# Wattuino-Uno_v11.net
KiCad netlist of a schematic drawn in EAGLE
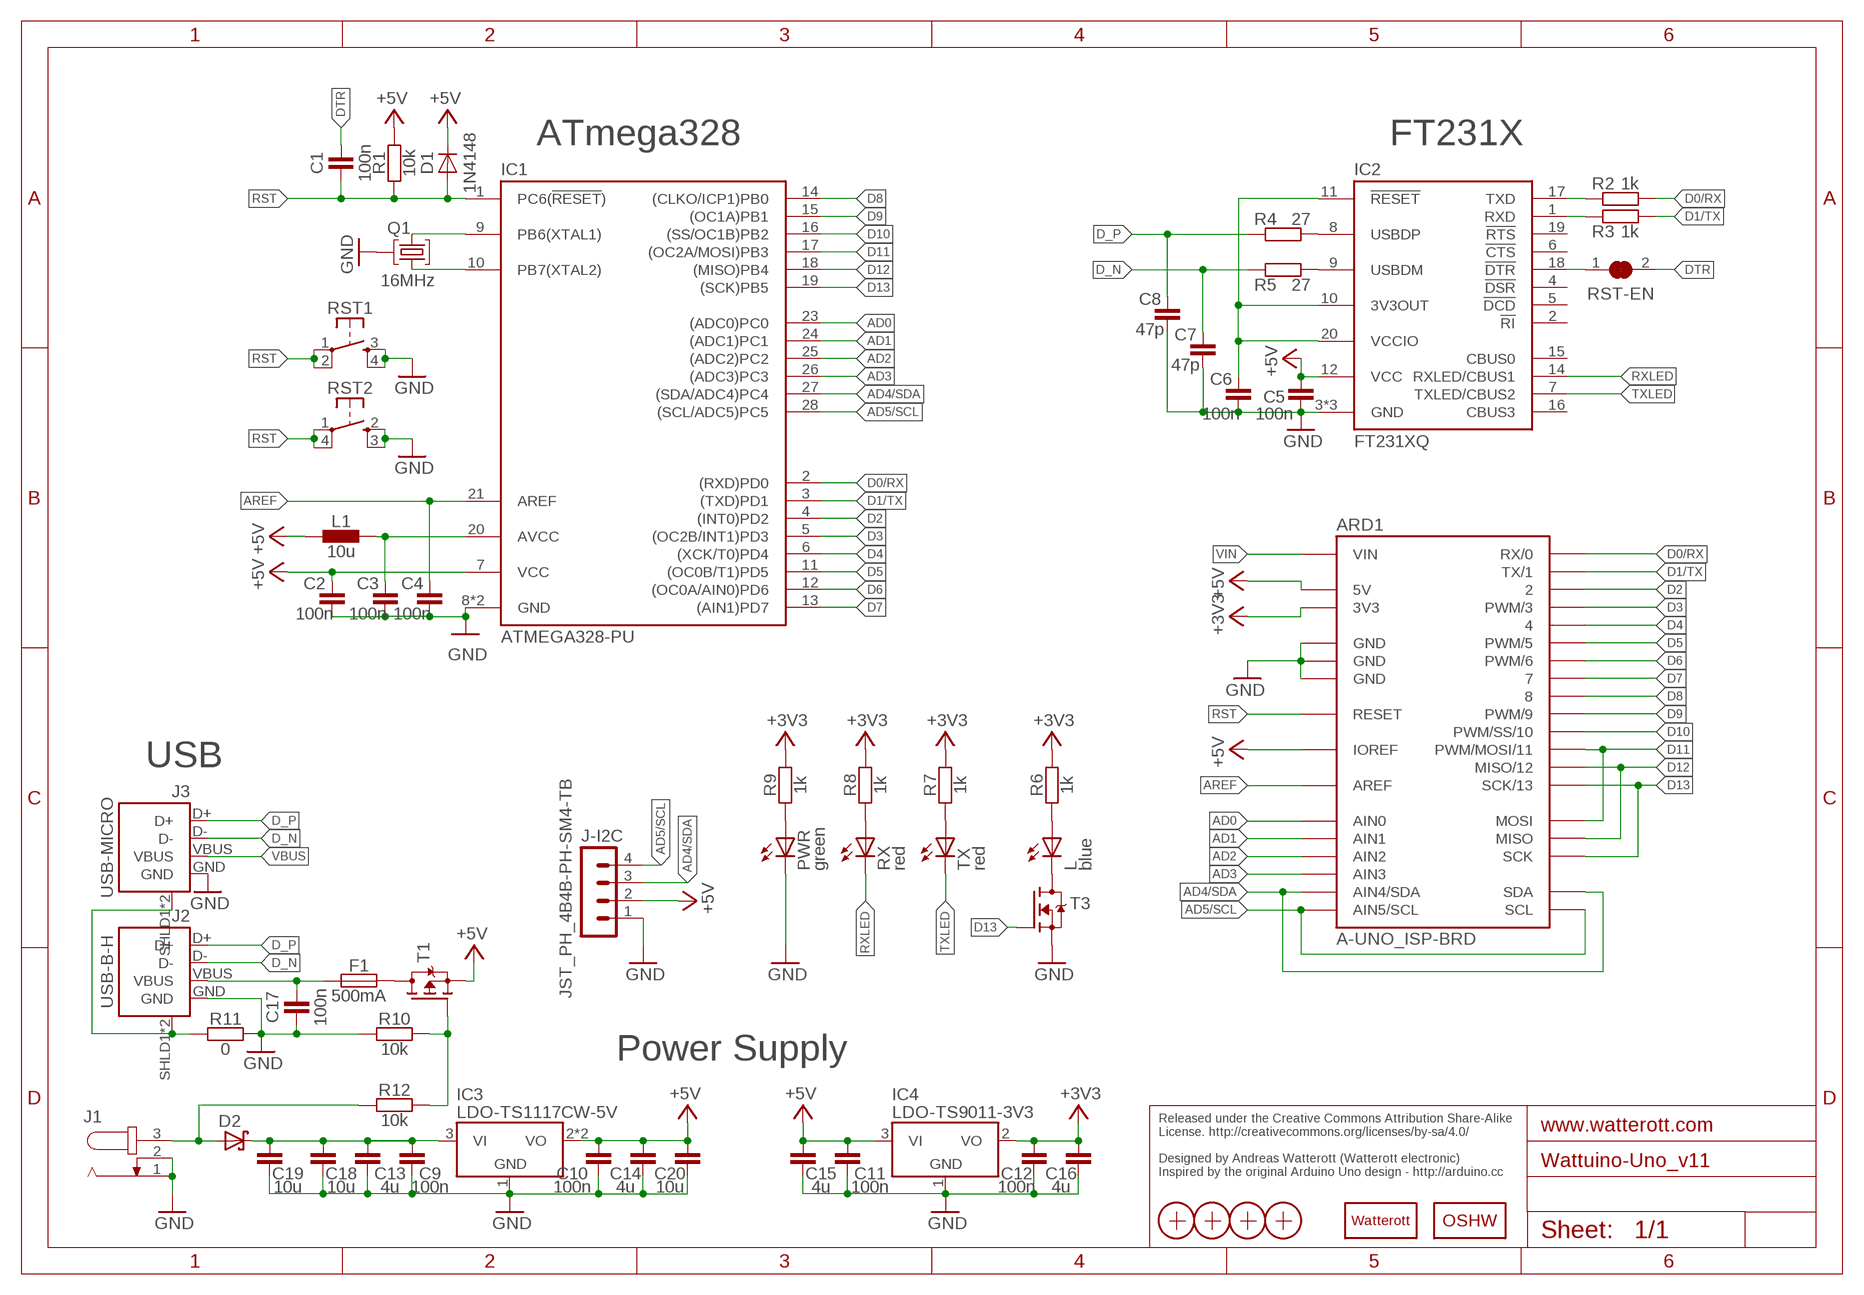
[diagram p0: schematic, sheet 1]

(export (version "E")
  (design (tool "Eeschema 10.0.6"))
  (components
    (comp (ref "ARD1")
      (value "A-UNO_ISP-BRD")
      (footprint "eagle-import:A-UNO-ISP")
      (libsource (lib "eagle-import") (part "A-UNO_ISP-BRD"))
    )
    (comp (ref "C1")
      (value "100n")
      (footprint "eagle-import:C0402")
      (libsource (lib "eagle-import") (part "CAPACITOR-0402"))
    )
    (comp (ref "C2")
      (value "100n")
      (footprint "eagle-import:C0402")
      (libsource (lib "eagle-import") (part "CAPACITOR-0402"))
    )
    (comp (ref "C3")
      (value "100n")
      (footprint "eagle-import:C0402")
      (libsource (lib "eagle-import") (part "CAPACITOR-0402"))
    )
    (comp (ref "C4")
      (value "100n")
      (footprint "eagle-import:C0402")
      (libsource (lib "eagle-import") (part "CAPACITOR-0402"))
    )
    (comp (ref "C5")
      (value "100n")
      (footprint "eagle-import:C0402")
      (libsource (lib "eagle-import") (part "CAPACITOR-0402"))
    )
    (comp (ref "C6")
      (value "100n")
      (footprint "eagle-import:C0402")
      (libsource (lib "eagle-import") (part "CAPACITOR-0402"))
    )
    (comp (ref "C7")
      (value "47p")
      (footprint "eagle-import:C0402")
      (libsource (lib "eagle-import") (part "CAPACITOR-0402"))
    )
    (comp (ref "C8")
      (value "47p")
      (footprint "eagle-import:C0402")
      (libsource (lib "eagle-import") (part "CAPACITOR-0402"))
    )
    (comp (ref "C9")
      (value "100n")
      (footprint "eagle-import:C0402")
      (libsource (lib "eagle-import") (part "CAPACITOR-0402"))
    )
    (comp (ref "C10")
      (value "100n")
      (footprint "eagle-import:C0402")
      (libsource (lib "eagle-import") (part "CAPACITOR-0402"))
    )
    (comp (ref "C11")
      (value "100n")
      (footprint "eagle-import:C0402")
      (libsource (lib "eagle-import") (part "CAPACITOR-0402"))
    )
    (comp (ref "C12")
      (value "100n")
      (footprint "eagle-import:C0402")
      (libsource (lib "eagle-import") (part "CAPACITOR-0402"))
    )
    (comp (ref "C13")
      (value "4u")
      (footprint "eagle-import:C0603")
      (libsource (lib "eagle-import") (part "CAPACITOR-0603"))
    )
    (comp (ref "C14")
      (value "4u")
      (footprint "eagle-import:C0603")
      (libsource (lib "eagle-import") (part "CAPACITOR-0603"))
    )
    (comp (ref "C15")
      (value "4u")
      (footprint "eagle-import:C0603")
      (libsource (lib "eagle-import") (part "CAPACITOR-0603"))
    )
    (comp (ref "C16")
      (value "4u")
      (footprint "eagle-import:C0603")
      (libsource (lib "eagle-import") (part "CAPACITOR-0603"))
    )
    (comp (ref "C17")
      (value "100n")
      (footprint "eagle-import:C0402")
      (libsource (lib "eagle-import") (part "CAPACITOR-0402"))
    )
    (comp (ref "C18")
      (value "10u")
      (footprint "eagle-import:C1206")
      (libsource (lib "eagle-import") (part "CAPACITOR-1206"))
    )
    (comp (ref "C19")
      (value "10u")
      (footprint "eagle-import:C1206")
      (libsource (lib "eagle-import") (part "CAPACITOR-1206"))
    )
    (comp (ref "C20")
      (value "10u")
      (footprint "eagle-import:C1206")
      (libsource (lib "eagle-import") (part "CAPACITOR-1206"))
    )
    (comp (ref "D1")
      (value "1N4148")
      (footprint "eagle-import:SOD110")
      (libsource (lib "eagle-import") (part "DIODE-SOD110"))
    )
    (comp (ref "D2")
      (value "D_SCHOTTKY-SMA")
      (footprint "eagle-import:SMA_DO214AC")
      (libsource (lib "eagle-import") (part "D_SCHOTTKY-SMA"))
    )
    (comp (ref "F1")
      (value "500mA")
      (footprint "eagle-import:C0805")
      (libsource (lib "eagle-import") (part "FUSE-0805"))
    )
    (comp (ref "IC1")
      (value "ATMEGA328-PU")
      (footprint "eagle-import:DIL28")
      (libsource (lib "eagle-import") (part "ATMEGA328-PU"))
    )
    (comp (ref "IC2")
      (value "FT231XQ")
      (footprint "eagle-import:QFN20-PAD")
      (libsource (lib "eagle-import") (part "FT231XQ"))
    )
    (comp (ref "IC3")
      (value "LDO-TS1117CW-5V")
      (footprint "eagle-import:SOT223")
      (libsource (lib "eagle-import") (part "LDO-TS1117CW-5V"))
    )
    (comp (ref "IC4")
      (value "LDO-TS9011-3V3")
      (footprint "eagle-import:SOT23")
      (libsource (lib "eagle-import") (part "LDO-TS9011-3V3"))
    )
    (comp (ref "J-I2C")
      (value "JST_PH_4B4B-PH-SM4-TB")
      (footprint "eagle-import:JST_B4B-PH-SM4-TB")
      (libsource (lib "eagle-import") (part "JST_PH_4B4B-PH-SM4-TB"))
    )
    (comp (ref "J1")
      (value "DC-JACK")
      (footprint "eagle-import:DC-JACK")
      (libsource (lib "eagle-import") (part "DC-JACK"))
    )
    (comp (ref "J2")
      (value "USB-B-H")
      (footprint "eagle-import:USB-B-H")
      (libsource (lib "eagle-import") (part "USB-B-H"))
    )
    (comp (ref "J3")
      (value "USB-MICRO")
      (footprint "eagle-import:USB-MICRO-10103594")
      (libsource (lib "eagle-import") (part "USB-MICRO"))
    )
    (comp (ref "L")
      (value "blue")
      (footprint "eagle-import:C0603")
      (libsource (lib "eagle-import") (part "LED-0603"))
    )
    (comp (ref "L1")
      (value "10u")
      (footprint "eagle-import:C0603")
      (libsource (lib "eagle-import") (part "INDUCTOR-0603"))
    )
    (comp (ref "LOGO1")
      (value "LOGO-S_PLACE_M")
      (footprint "eagle-import:SPARK_TPLACE_M")
      (libsource (lib "eagle-import") (part "LOGO-S_PLACE_M"))
    )
    (comp (ref "LOGO2")
      (value "OSHW_LOGOX0100")
      (footprint "eagle-import:OSHW_6X100")
      (libsource (lib "eagle-import") (part "OSHW_LOGOX0100"))
    )
    (comp (ref "PWR")
      (value "green")
      (footprint "eagle-import:C0603")
      (libsource (lib "eagle-import") (part "LED-0603"))
    )
    (comp (ref "Q1")
      (value "16MHz")
      (footprint "eagle-import:CRYSTAL_32X13")
      (libsource (lib "eagle-import") (part "CRYSTAL-RES-32"))
    )
    (comp (ref "R1")
      (value "10k")
      (footprint "eagle-import:C0402")
      (libsource (lib "eagle-import") (part "RESISTOR-0402"))
    )
    (comp (ref "R2")
      (value "1k")
      (footprint "eagle-import:C0402")
      (libsource (lib "eagle-import") (part "RESISTOR-0402"))
    )
    (comp (ref "R3")
      (value "1k")
      (footprint "eagle-import:C0402")
      (libsource (lib "eagle-import") (part "RESISTOR-0402"))
    )
    (comp (ref "R4")
      (value "27")
      (footprint "eagle-import:C0402")
      (libsource (lib "eagle-import") (part "RESISTOR-0402"))
    )
    (comp (ref "R5")
      (value "27")
      (footprint "eagle-import:C0402")
      (libsource (lib "eagle-import") (part "RESISTOR-0402"))
    )
    (comp (ref "R6")
      (value "1k")
      (footprint "eagle-import:C0402")
      (libsource (lib "eagle-import") (part "RESISTOR-0402"))
    )
    (comp (ref "R7")
      (value "1k")
      (footprint "eagle-import:C0402")
      (libsource (lib "eagle-import") (part "RESISTOR-0402"))
    )
    (comp (ref "R8")
      (value "1k")
      (footprint "eagle-import:C0402")
      (libsource (lib "eagle-import") (part "RESISTOR-0402"))
    )
    (comp (ref "R9")
      (value "1k")
      (footprint "eagle-import:C0402")
      (libsource (lib "eagle-import") (part "RESISTOR-0402"))
    )
    (comp (ref "R10")
      (value "10k")
      (footprint "eagle-import:C0402")
      (libsource (lib "eagle-import") (part "RESISTOR-0402"))
    )
    (comp (ref "R11")
      (value "0")
      (footprint "eagle-import:C0402")
      (libsource (lib "eagle-import") (part "RESISTOR-0402"))
    )
    (comp (ref "R12")
      (value "10k")
      (footprint "eagle-import:C0402")
      (libsource (lib "eagle-import") (part "RESISTOR-0402"))
    )
    (comp (ref "RST-EN")
      (value "JUMPER2-0603")
      (footprint "eagle-import:JUMPER2-0603")
      (libsource (lib "eagle-import") (part "JUMPER2-0603"))
    )
    (comp (ref "RST1")
      (value "SW-TACTILE-PTS840P")
      (footprint "eagle-import:PTS840P")
      (libsource (lib "eagle-import") (part "SW-TACTILE-PTS840P"))
    )
    (comp (ref "RST2")
      (value "SW-TACTILE-TL3315")
      (footprint "eagle-import:TL3315N")
      (libsource (lib "eagle-import") (part "SW-TACTILE-TL3315"))
    )
    (comp (ref "RX")
      (value "red")
      (footprint "eagle-import:C0603")
      (libsource (lib "eagle-import") (part "LED-0603"))
    )
    (comp (ref "T1")
      (value "MOSFET-P-SOT23")
      (footprint "eagle-import:SOT23")
      (libsource (lib "eagle-import") (part "MOSFET-P-SOT23"))
    )
    (comp (ref "T3")
      (value "MOSFET-N-SOT23")
      (footprint "eagle-import:SOT23")
      (libsource (lib "eagle-import") (part "MOSFET-N-SOT23"))
    )
    (comp (ref "TX")
      (value "red")
      (footprint "eagle-import:C0603")
      (libsource (lib "eagle-import") (part "LED-0603"))
    )
    (comp (ref "X1")
      (value "PASSER-07")
      (footprint "eagle-import:PASSER_07MM")
      (libsource (lib "eagle-import") (part "PASSER-07"))
    )
    (comp (ref "X2")
      (value "PASSER-07")
      (footprint "eagle-import:PASSER_07MM")
      (libsource (lib "eagle-import") (part "PASSER-07"))
    )
    (comp (ref "X3")
      (value "PASSER-07")
      (footprint "eagle-import:PASSER_07MM")
      (libsource (lib "eagle-import") (part "PASSER-07"))
    )
    (comp (ref "X4")
      (value "PASSER-07")
      (footprint "eagle-import:PASSER_07MM")
      (libsource (lib "eagle-import") (part "PASSER-07"))
    )
  )
  (nets
    (net (code "1") (name "+3V3") (class "Default")
      (node (ref "ARD1") (pin "3V3") (pinfunction "3V3_3V3") (pintype "power_in"))
      (node (ref "C12") (pin "2") (pinfunction "2_2") (pintype "passive"))
      (node (ref "C16") (pin "2") (pinfunction "2_2") (pintype "passive"))
      (node (ref "IC4") (pin "2") (pinfunction "VO_2") (pintype "passive"))
      (node (ref "R6") (pin "2") (pinfunction "2_2") (pintype "passive"))
      (node (ref "R7") (pin "2") (pinfunction "2_2") (pintype "passive"))
      (node (ref "R8") (pin "2") (pinfunction "2_2") (pintype "passive"))
      (node (ref "R9") (pin "2") (pinfunction "2_2") (pintype "passive"))
    )
    (net (code "2") (name "+5V") (class "Default")
      (node (ref "ARD1") (pin "5V") (pinfunction "5V_5V") (pintype "power_in"))
      (node (ref "ARD1") (pin "IOREF") (pinfunction "IOREF_IOREF") (pintype "power_in"))
      (node (ref "ARD1") (pin "VCC") (pinfunction "5V_VCC") (pintype "power_in"))
      (node (ref "C10") (pin "2") (pinfunction "2_2") (pintype "passive"))
      (node (ref "C11") (pin "2") (pinfunction "2_2") (pintype "passive"))
      (node (ref "C14") (pin "2") (pinfunction "2_2") (pintype "passive"))
      (node (ref "C15") (pin "2") (pinfunction "2_2") (pintype "passive"))
      (node (ref "C2") (pin "2") (pinfunction "2_2") (pintype "passive"))
      (node (ref "C20") (pin "2") (pinfunction "2_2") (pintype "passive"))
      (node (ref "C5") (pin "2") (pinfunction "2_2") (pintype "passive"))
      (node (ref "D1") (pin "C") (pinfunction "C_C") (pintype "passive"))
      (node (ref "IC1") (pin "7") (pinfunction "VCC_7") (pintype "power_in"))
      (node (ref "IC2") (pin "12") (pinfunction "VCC_12") (pintype "power_in"))
      (node (ref "IC3") (pin "2") (pinfunction "VO_2") (pintype "passive"))
      (node (ref "IC3") (pin "4") (pinfunction "VO_4") (pintype "passive"))
      (node (ref "IC4") (pin "3") (pinfunction "VI_3") (pintype "input"))
      (node (ref "J-I2C") (pin "2") (pinfunction "2_2") (pintype "passive"))
      (node (ref "L1") (pin "1") (pinfunction "1_1") (pintype "passive"))
      (node (ref "R1") (pin "2") (pinfunction "2_2") (pintype "passive"))
      (node (ref "T1") (pin "2") (pinfunction "S_2") (pintype "passive"))
    )
    (net (code "3") (name "AD0") (class "Default")
      (node (ref "ARD1") (pin "A0") (pinfunction "AIN0_A0") (pintype "bidirectional"))
      (node (ref "IC1") (pin "23") (pinfunction "(ADC0)PC0_23") (pintype "bidirectional"))
    )
    (net (code "4") (name "AD1") (class "Default")
      (node (ref "ARD1") (pin "A1") (pinfunction "AIN1_A1") (pintype "bidirectional"))
      (node (ref "IC1") (pin "24") (pinfunction "(ADC1)PC1_24") (pintype "bidirectional"))
    )
    (net (code "5") (name "AD2") (class "Default")
      (node (ref "ARD1") (pin "A2") (pinfunction "AIN2_A2") (pintype "bidirectional"))
      (node (ref "IC1") (pin "25") (pinfunction "(ADC2)PC2_25") (pintype "bidirectional"))
    )
    (net (code "6") (name "AD3") (class "Default")
      (node (ref "ARD1") (pin "A3") (pinfunction "AIN3_A3") (pintype "bidirectional"))
      (node (ref "IC1") (pin "26") (pinfunction "(ADC3)PC3_26") (pintype "bidirectional"))
    )
    (net (code "7") (name "AD4{slash}SDA") (class "Default")
      (node (ref "ARD1") (pin "A4") (pinfunction "AIN4/SDA_A4") (pintype "bidirectional"))
      (node (ref "ARD1") (pin "SDA") (pinfunction "SDA_SDA") (pintype "bidirectional"))
      (node (ref "IC1") (pin "27") (pinfunction "(SDA/ADC4)PC4_27") (pintype "bidirectional"))
      (node (ref "J-I2C") (pin "3") (pinfunction "3_3") (pintype "passive"))
    )
    (net (code "8") (name "AD5{slash}SCL") (class "Default")
      (node (ref "ARD1") (pin "A5") (pinfunction "AIN5/SCL_A5") (pintype "bidirectional"))
      (node (ref "ARD1") (pin "SCL") (pinfunction "SCL_SCL") (pintype "bidirectional"))
      (node (ref "IC1") (pin "28") (pinfunction "(SCL/ADC5)PC5_28") (pintype "bidirectional"))
      (node (ref "J-I2C") (pin "4") (pinfunction "4_4") (pintype "passive"))
    )
    (net (code "9") (name "AREF") (class "Default")
      (node (ref "ARD1") (pin "AREF") (pinfunction "AREF_AREF") (pintype "power_in"))
      (node (ref "C4") (pin "2") (pinfunction "2_2") (pintype "passive"))
      (node (ref "IC1") (pin "21") (pinfunction "AREF_21") (pintype "passive"))
    )
    (net (code "10") (name "D0{slash}RX") (class "Default")
      (node (ref "ARD1") (pin "0") (pinfunction "RX/0_0") (pintype "bidirectional"))
      (node (ref "IC1") (pin "2") (pinfunction "(RXD)PD0_2") (pintype "bidirectional"))
      (node (ref "R2") (pin "2") (pinfunction "2_2") (pintype "passive"))
    )
    (net (code "11") (name "D1{slash}TX") (class "Default")
      (node (ref "ARD1") (pin "1") (pinfunction "TX/1_1") (pintype "bidirectional"))
      (node (ref "IC1") (pin "3") (pinfunction "(TXD)PD1_3") (pintype "bidirectional"))
      (node (ref "R3") (pin "2") (pinfunction "2_2") (pintype "passive"))
    )
    (net (code "12") (name "D2") (class "Default")
      (node (ref "ARD1") (pin "2") (pinfunction "2_2") (pintype "bidirectional"))
      (node (ref "IC1") (pin "4") (pinfunction "(INT0)PD2_4") (pintype "bidirectional"))
    )
    (net (code "13") (name "D3") (class "Default")
      (node (ref "ARD1") (pin "3") (pinfunction "PWM/3_3") (pintype "bidirectional"))
      (node (ref "IC1") (pin "5") (pinfunction "(OC2B/INT1)PD3_5") (pintype "bidirectional"))
    )
    (net (code "14") (name "D4") (class "Default")
      (node (ref "ARD1") (pin "4") (pinfunction "4_4") (pintype "bidirectional"))
      (node (ref "IC1") (pin "6") (pinfunction "(XCK/T0)PD4_6") (pintype "bidirectional"))
    )
    (net (code "15") (name "D5") (class "Default")
      (node (ref "ARD1") (pin "5") (pinfunction "PWM/5_5") (pintype "bidirectional"))
      (node (ref "IC1") (pin "11") (pinfunction "(OC0B/T1)PD5_11") (pintype "bidirectional"))
    )
    (net (code "16") (name "D6") (class "Default")
      (node (ref "ARD1") (pin "6") (pinfunction "PWM/6_6") (pintype "bidirectional"))
      (node (ref "IC1") (pin "12") (pinfunction "(OC0A/AIN0)PD6_12") (pintype "bidirectional"))
    )
    (net (code "17") (name "D7") (class "Default")
      (node (ref "ARD1") (pin "7") (pinfunction "7_7") (pintype "bidirectional"))
      (node (ref "IC1") (pin "13") (pinfunction "(AIN1)PD7_13") (pintype "bidirectional"))
    )
    (net (code "18") (name "D8") (class "Default")
      (node (ref "ARD1") (pin "8") (pinfunction "8_8") (pintype "bidirectional"))
      (node (ref "IC1") (pin "14") (pinfunction "(CLKO/ICP1)PB0_14") (pintype "bidirectional"))
    )
    (net (code "19") (name "D9") (class "Default")
      (node (ref "ARD1") (pin "9") (pinfunction "PWM/9_9") (pintype "bidirectional"))
      (node (ref "IC1") (pin "15") (pinfunction "(OC1A)PB1_15") (pintype "bidirectional"))
    )
    (net (code "20") (name "D10") (class "Default")
      (node (ref "ARD1") (pin "10") (pinfunction "PWM/SS/10_10") (pintype "bidirectional"))
      (node (ref "IC1") (pin "16") (pinfunction "(SS/OC1B)PB2_16") (pintype "bidirectional"))
    )
    (net (code "21") (name "D11") (class "Default")
      (node (ref "ARD1") (pin "11") (pinfunction "PWM/MOSI/11_11") (pintype "bidirectional"))
      (node (ref "ARD1") (pin "MOSI") (pinfunction "MOSI_MOSI") (pintype "bidirectional"))
      (node (ref "IC1") (pin "17") (pinfunction "(OC2A/MOSI)PB3_17") (pintype "bidirectional"))
    )
    (net (code "22") (name "D12") (class "Default")
      (node (ref "ARD1") (pin "12") (pinfunction "MISO/12_12") (pintype "bidirectional"))
      (node (ref "ARD1") (pin "MISO") (pinfunction "MISO_MISO") (pintype "bidirectional"))
      (node (ref "IC1") (pin "18") (pinfunction "(MISO)PB4_18") (pintype "bidirectional"))
    )
    (net (code "23") (name "D13") (class "Default")
      (node (ref "ARD1") (pin "13") (pinfunction "SCK/13_13") (pintype "bidirectional"))
      (node (ref "ARD1") (pin "SCK") (pinfunction "SCK_SCK") (pintype "bidirectional"))
      (node (ref "IC1") (pin "19") (pinfunction "(SCK)PB5_19") (pintype "bidirectional"))
      (node (ref "T3") (pin "1") (pinfunction "G_1") (pintype "passive"))
    )
    (net (code "24") (name "DTR") (class "Default")
      (node (ref "C1") (pin "2") (pinfunction "2_2") (pintype "passive"))
      (node (ref "RST-EN") (pin "2") (pinfunction "2_2") (pintype "passive"))
    )
    (net (code "25") (name "D_N") (class "Default")
      (node (ref "C7") (pin "2") (pinfunction "2_2") (pintype "passive"))
      (node (ref "J2") (pin "D-") (pinfunction "D-_D-") (pintype "bidirectional"))
      (node (ref "J3") (pin "D-") (pinfunction "D-_D-") (pintype "bidirectional"))
      (node (ref "R5") (pin "1") (pinfunction "1_1") (pintype "passive"))
    )
    (net (code "26") (name "D_P") (class "Default")
      (node (ref "C8") (pin "2") (pinfunction "2_2") (pintype "passive"))
      (node (ref "J2") (pin "D+") (pinfunction "D+_D+") (pintype "bidirectional"))
      (node (ref "J3") (pin "D+") (pinfunction "D+_D+") (pintype "bidirectional"))
      (node (ref "R4") (pin "1") (pinfunction "1_1") (pintype "passive"))
    )
    (net (code "27") (name "GND") (class "Default")
      (node (ref "ARD1") (pin "GND@1") (pinfunction "GND_GND@1") (pintype "power_in"))
      (node (ref "ARD1") (pin "GND@2") (pinfunction "GND_GND@2") (pintype "power_in"))
      (node (ref "ARD1") (pin "GND@3") (pinfunction "GND_GND@3") (pintype "power_in"))
      (node (ref "ARD1") (pin "GND@4") (pinfunction "GND_GND@4") (pintype "power_in"))
      (node (ref "C10") (pin "1") (pinfunction "1_1") (pintype "passive"))
      (node (ref "C11") (pin "1") (pinfunction "1_1") (pintype "passive"))
      (node (ref "C12") (pin "1") (pinfunction "1_1") (pintype "passive"))
      (node (ref "C13") (pin "1") (pinfunction "1_1") (pintype "passive"))
      (node (ref "C14") (pin "1") (pinfunction "1_1") (pintype "passive"))
      (node (ref "C15") (pin "1") (pinfunction "1_1") (pintype "passive"))
      (node (ref "C16") (pin "1") (pinfunction "1_1") (pintype "passive"))
      (node (ref "C17") (pin "1") (pinfunction "1_1") (pintype "passive"))
      (node (ref "C18") (pin "1") (pinfunction "1_1") (pintype "passive"))
      (node (ref "C19") (pin "1") (pinfunction "1_1") (pintype "passive"))
      (node (ref "C2") (pin "1") (pinfunction "1_1") (pintype "passive"))
      (node (ref "C20") (pin "1") (pinfunction "1_1") (pintype "passive"))
      (node (ref "C3") (pin "1") (pinfunction "1_1") (pintype "passive"))
      (node (ref "C4") (pin "1") (pinfunction "1_1") (pintype "passive"))
      (node (ref "C5") (pin "1") (pinfunction "1_1") (pintype "passive"))
      (node (ref "C6") (pin "1") (pinfunction "1_1") (pintype "passive"))
      (node (ref "C7") (pin "1") (pinfunction "1_1") (pintype "passive"))
      (node (ref "C8") (pin "1") (pinfunction "1_1") (pintype "passive"))
      (node (ref "C9") (pin "1") (pinfunction "1_1") (pintype "passive"))
      (node (ref "IC1") (pin "22") (pinfunction "GND_22") (pintype "power_in"))
      (node (ref "IC1") (pin "8") (pinfunction "GND_8") (pintype "power_in"))
      (node (ref "IC2") (pin "13") (pinfunction "GND_13") (pintype "power_in"))
      (node (ref "IC2") (pin "3") (pinfunction "GND_3") (pintype "power_in"))
      (node (ref "IC2") (pin "TP") (pinfunction "GND_TP") (pintype "power_in"))
      (node (ref "IC3") (pin "1") (pinfunction "GND_1") (pintype "passive"))
      (node (ref "IC4") (pin "1") (pinfunction "GND_1") (pintype "passive"))
      (node (ref "J-I2C") (pin "1") (pinfunction "1_1") (pintype "passive"))
      (node (ref "J1") (pin "1") (pinfunction "1_1") (pintype "passive"))
      (node (ref "J1") (pin "2") (pinfunction "2_2") (pintype "passive"))
      (node (ref "J2") (pin "GND") (pinfunction "GND_GND") (pintype "power_in"))
      (node (ref "J3") (pin "GND") (pinfunction "GND_GND") (pintype "power_in"))
      (node (ref "PWR") (pin "C") (pinfunction "C_C") (pintype "passive"))
      (node (ref "Q1") (pin "GND") (pinfunction "GND_GND") (pintype "passive"))
      (node (ref "R10") (pin "1") (pinfunction "1_1") (pintype "passive"))
      (node (ref "R11") (pin "2") (pinfunction "2_2") (pintype "passive"))
      (node (ref "RST1") (pin "3") (pinfunction "S1_3") (pintype "passive"))
      (node (ref "RST1") (pin "4") (pinfunction "S2_4") (pintype "passive"))
      (node (ref "RST2") (pin "2") (pinfunction "S1_2") (pintype "passive"))
      (node (ref "RST2") (pin "3") (pinfunction "S2_3") (pintype "passive"))
      (node (ref "T3") (pin "2") (pinfunction "S_2") (pintype "passive"))
    )
    (net (code "28") (name "Net-(D2-PadA)") (class "Default")
      (node (ref "D2") (pin "A") (pinfunction "A_A") (pintype "passive"))
      (node (ref "J1") (pin "3") (pinfunction "3_3") (pintype "passive"))
      (node (ref "R12") (pin "1") (pinfunction "1_1") (pintype "passive"))
    )
    (net (code "29") (name "Net-(IC1-AVCC)") (class "Default")
      (node (ref "C3") (pin "2") (pinfunction "2_2") (pintype "passive"))
      (node (ref "IC1") (pin "20") (pinfunction "AVCC_20") (pintype "power_in"))
      (node (ref "L1") (pin "2") (pinfunction "2_2") (pintype "passive"))
    )
    (net (code "30") (name "Net-(IC1-PB6(XTAL1))") (class "Default")
      (node (ref "IC1") (pin "9") (pinfunction "PB6(XTAL1)_9") (pintype "bidirectional"))
      (node (ref "Q1") (pin "2") (pinfunction "2_2") (pintype "passive"))
    )
    (net (code "31") (name "Net-(IC1-PB7(XTAL2))") (class "Default")
      (node (ref "IC1") (pin "10") (pinfunction "PB7(XTAL2)_10") (pintype "bidirectional"))
      (node (ref "Q1") (pin "1") (pinfunction "1_1") (pintype "passive"))
    )
    (net (code "32") (name "Net-(IC2-3V3OUT)") (class "Default")
      (node (ref "C6") (pin "2") (pinfunction "2_2") (pintype "passive"))
      (node (ref "IC2") (pin "10") (pinfunction "3V3OUT_10") (pintype "power_in"))
      (node (ref "IC2") (pin "11") (pinfunction "~{RESET}_11") (pintype "bidirectional"))
      (node (ref "IC2") (pin "20") (pinfunction "VCCIO_20") (pintype "power_in"))
    )
    (net (code "33") (name "Net-(IC2-RXD)") (class "Default")
      (node (ref "IC2") (pin "1") (pinfunction "RXD_1") (pintype "bidirectional"))
      (node (ref "R3") (pin "1") (pinfunction "1_1") (pintype "passive"))
    )
    (net (code "34") (name "Net-(IC2-TXD)") (class "Default")
      (node (ref "IC2") (pin "17") (pinfunction "TXD_17") (pintype "bidirectional"))
      (node (ref "R2") (pin "1") (pinfunction "1_1") (pintype "passive"))
    )
    (net (code "35") (name "Net-(IC2-USBDM)") (class "Default")
      (node (ref "IC2") (pin "9") (pinfunction "USBDM_9") (pintype "bidirectional"))
      (node (ref "R5") (pin "2") (pinfunction "2_2") (pintype "passive"))
    )
    (net (code "36") (name "Net-(IC2-USBDP)") (class "Default")
      (node (ref "IC2") (pin "8") (pinfunction "USBDP_8") (pintype "bidirectional"))
      (node (ref "R4") (pin "2") (pinfunction "2_2") (pintype "passive"))
    )
    (net (code "37") (name "Net-(IC2-~{DTR})") (class "Default")
      (node (ref "IC2") (pin "18") (pinfunction "~{DTR}_18") (pintype "bidirectional"))
      (node (ref "RST-EN") (pin "1") (pinfunction "1_1") (pintype "passive"))
    )
    (net (code "38") (name "Net-(J2-SHIELD-PadSHLD1)") (class "Default")
      (node (ref "J2") (pin "SHLD1") (pinfunction "SHIELD_SHLD1") (pintype "passive"))
      (node (ref "J2") (pin "SHLD2") (pinfunction "SHIELD_SHLD2") (pintype "passive"))
      (node (ref "J3") (pin "SHLD1") (pinfunction "SHIELD_SHLD1") (pintype "passive"))
      (node (ref "J3") (pin "SHLD2") (pinfunction "SHIELD_SHLD2") (pintype "passive"))
      (node (ref "R11") (pin "1") (pinfunction "1_1") (pintype "passive"))
    )
    (net (code "39") (name "Net-(L-PadA)") (class "Default")
      (node (ref "L") (pin "A") (pinfunction "A_A") (pintype "passive"))
      (node (ref "R6") (pin "1") (pinfunction "1_1") (pintype "passive"))
    )
    (net (code "40") (name "Net-(PWR-PadA)") (class "Default")
      (node (ref "PWR") (pin "A") (pinfunction "A_A") (pintype "passive"))
      (node (ref "R9") (pin "1") (pinfunction "1_1") (pintype "passive"))
    )
    (net (code "41") (name "Net-(R7-Pad1)") (class "Default")
      (node (ref "R7") (pin "1") (pinfunction "1_1") (pintype "passive"))
      (node (ref "TX") (pin "A") (pinfunction "A_A") (pintype "passive"))
    )
    (net (code "42") (name "Net-(R8-Pad1)") (class "Default")
      (node (ref "R8") (pin "1") (pinfunction "1_1") (pintype "passive"))
      (node (ref "RX") (pin "A") (pinfunction "A_A") (pintype "passive"))
    )
    (net (code "43") (name "Net-(T1-D)") (class "Default")
      (node (ref "F1") (pin "2") (pinfunction "2_2") (pintype "passive"))
      (node (ref "T1") (pin "3") (pinfunction "D_3") (pintype "passive"))
    )
    (net (code "44") (name "Net-(T1-G)") (class "Default")
      (node (ref "R10") (pin "2") (pinfunction "2_2") (pintype "passive"))
      (node (ref "R12") (pin "2") (pinfunction "2_2") (pintype "passive"))
      (node (ref "T1") (pin "1") (pinfunction "G_1") (pintype "passive"))
    )
    (net (code "45") (name "Net-(T3-D)") (class "Default")
      (node (ref "L") (pin "C") (pinfunction "C_C") (pintype "passive"))
      (node (ref "T3") (pin "3") (pinfunction "D_3") (pintype "passive"))
    )
    (net (code "46") (name "RST") (class "Default")
      (node (ref "ARD1") (pin "RST@1") (pinfunction "RESET_RST@1") (pintype "bidirectional"))
      (node (ref "ARD1") (pin "RST@2") (pinfunction "RESET_RST@2") (pintype "bidirectional"))
      (node (ref "C1") (pin "1") (pinfunction "1_1") (pintype "passive"))
      (node (ref "D1") (pin "A") (pinfunction "A_A") (pintype "passive"))
      (node (ref "IC1") (pin "1") (pinfunction "PC6(~{RESET})_1") (pintype "bidirectional"))
      (node (ref "R1") (pin "1") (pinfunction "1_1") (pintype "passive"))
      (node (ref "RST1") (pin "1") (pinfunction "P1_1") (pintype "passive"))
      (node (ref "RST1") (pin "2") (pinfunction "P2_2") (pintype "passive"))
      (node (ref "RST2") (pin "1") (pinfunction "P1_1") (pintype "passive"))
      (node (ref "RST2") (pin "4") (pinfunction "P2_4") (pintype "passive"))
    )
    (net (code "47") (name "RXLED") (class "Default")
      (node (ref "IC2") (pin "14") (pinfunction "RXLED/CBUS1_14") (pintype "bidirectional"))
      (node (ref "RX") (pin "C") (pinfunction "C_C") (pintype "passive"))
    )
    (net (code "48") (name "TXLED") (class "Default")
      (node (ref "IC2") (pin "7") (pinfunction "TXLED/CBUS2_7") (pintype "bidirectional"))
      (node (ref "TX") (pin "C") (pinfunction "C_C") (pintype "passive"))
    )
    (net (code "49") (name "VBUS") (class "Default")
      (node (ref "C17") (pin "2") (pinfunction "2_2") (pintype "passive"))
      (node (ref "F1") (pin "1") (pinfunction "1_1") (pintype "passive"))
      (node (ref "J2") (pin "VBUS") (pinfunction "VBUS_VBUS") (pintype "power_in"))
      (node (ref "J3") (pin "VBUS") (pinfunction "VBUS_VBUS") (pintype "power_in"))
    )
    (net (code "50") (name "VIN") (class "Default")
      (node (ref "ARD1") (pin "VIN") (pinfunction "VIN_VIN") (pintype "power_in"))
      (node (ref "C13") (pin "2") (pinfunction "2_2") (pintype "passive"))
      (node (ref "C18") (pin "2") (pinfunction "2_2") (pintype "passive"))
      (node (ref "C19") (pin "2") (pinfunction "2_2") (pintype "passive"))
      (node (ref "C9") (pin "2") (pinfunction "2_2") (pintype "passive"))
      (node (ref "D2") (pin "C") (pinfunction "C_C") (pintype "passive"))
      (node (ref "IC3") (pin "3") (pinfunction "VI_3") (pintype "input"))
    )
    (net (code "51") (name "unconnected-(IC2-CBUS0-Pad15)") (class "Default")
      (node (ref "IC2") (pin "15") (pinfunction "CBUS0_15") (pintype "bidirectional"))
    )
    (net (code "52") (name "unconnected-(IC2-CBUS3-Pad16)") (class "Default")
      (node (ref "IC2") (pin "16") (pinfunction "CBUS3_16") (pintype "bidirectional"))
    )
    (net (code "53") (name "unconnected-(IC2-~{CTS}-Pad6)") (class "Default")
      (node (ref "IC2") (pin "6") (pinfunction "~{CTS}_6") (pintype "bidirectional"))
    )
    (net (code "54") (name "unconnected-(IC2-~{DCD}-Pad5)") (class "Default")
      (node (ref "IC2") (pin "5") (pinfunction "~{DCD}_5") (pintype "bidirectional"))
    )
    (net (code "55") (name "unconnected-(IC2-~{DSR}-Pad4)") (class "Default")
      (node (ref "IC2") (pin "4") (pinfunction "~{DSR}_4") (pintype "bidirectional"))
    )
    (net (code "56") (name "unconnected-(IC2-~{RI}-Pad2)") (class "Default")
      (node (ref "IC2") (pin "2") (pinfunction "~{RI}_2") (pintype "bidirectional"))
    )
    (net (code "57") (name "unconnected-(IC2-~{RTS}-Pad19)") (class "Default")
      (node (ref "IC2") (pin "19") (pinfunction "~{RTS}_19") (pintype "bidirectional"))
    )
  )
)
